# Power_Amp.net
KiCad netlist of a schematic drawn in Altium Designer
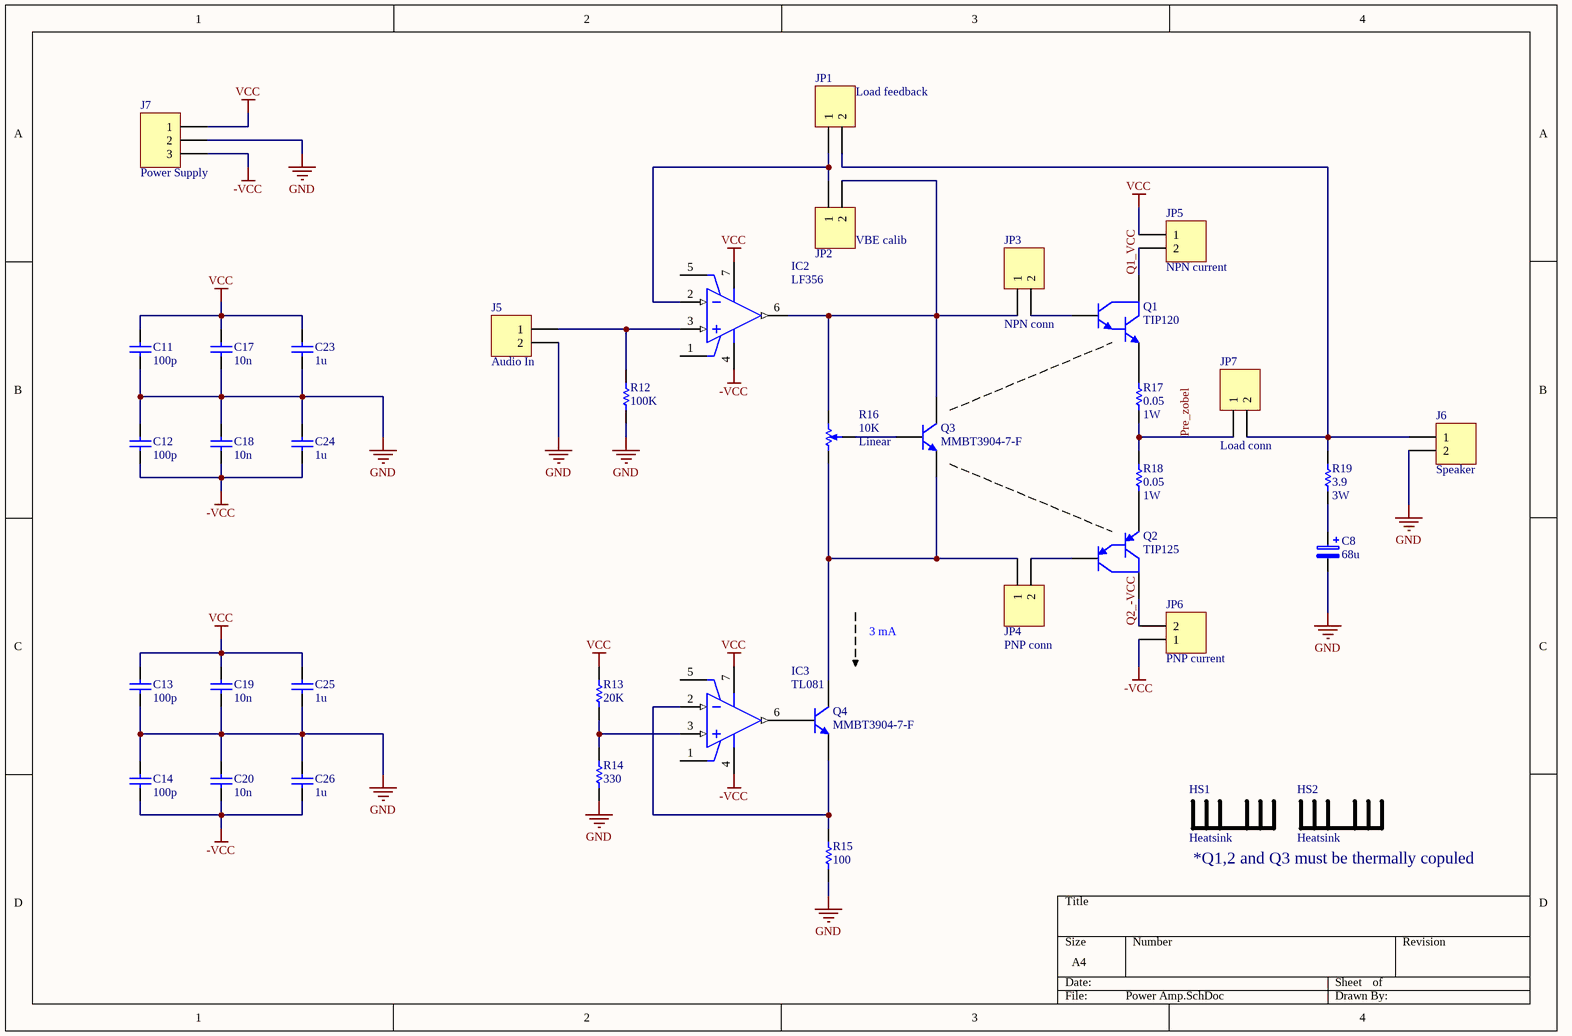
[diagram p0: Power Amp.SchDoc]

(export (version "E")
  (design (tool "Eeschema 10.0.6"))
  (components
    (comp (ref "C8")
      (value "68u")
      (footprint "CRADIAL-2.5mm")
      (description "Polarized Capacitor")
      (libsource (lib "nucleoduro_lib_audio") (part "Pol Capacitor"))
    )
    (comp (ref "C11")
      (value "100p")
      (footprint "C0805")
      (description "Capacitor")
      (libsource (lib "nucleoduro_lib_audio") (part "Capacitor"))
    )
    (comp (ref "C12")
      (value "100p")
      (footprint "C0805")
      (description "Capacitor")
      (libsource (lib "nucleoduro_lib_audio") (part "Capacitor"))
    )
    (comp (ref "C13")
      (value "100p")
      (footprint "C0805")
      (description "Capacitor")
      (libsource (lib "nucleoduro_lib_audio") (part "Capacitor"))
    )
    (comp (ref "C14")
      (value "100p")
      (footprint "C0805")
      (description "Capacitor")
      (libsource (lib "nucleoduro_lib_audio") (part "Capacitor"))
    )
    (comp (ref "C17")
      (value "10n")
      (footprint "C0805")
      (description "Capacitor")
      (libsource (lib "nucleoduro_lib_audio") (part "Capacitor"))
    )
    (comp (ref "C18")
      (value "10n")
      (footprint "C0805")
      (description "Capacitor")
      (libsource (lib "nucleoduro_lib_audio") (part "Capacitor"))
    )
    (comp (ref "C19")
      (value "10n")
      (footprint "C0805")
      (description "Capacitor")
      (libsource (lib "nucleoduro_lib_audio") (part "Capacitor"))
    )
    (comp (ref "C20")
      (value "10n")
      (footprint "C0805")
      (description "Capacitor")
      (libsource (lib "nucleoduro_lib_audio") (part "Capacitor"))
    )
    (comp (ref "C23")
      (value "1u")
      (footprint "C0805")
      (description "Capacitor")
      (libsource (lib "nucleoduro_lib_audio") (part "Capacitor"))
    )
    (comp (ref "C24")
      (value "1u")
      (footprint "C0805")
      (description "Capacitor")
      (libsource (lib "nucleoduro_lib_audio") (part "Capacitor"))
    )
    (comp (ref "C25")
      (value "1u")
      (footprint "C0805")
      (description "Capacitor")
      (libsource (lib "nucleoduro_lib_audio") (part "Capacitor"))
    )
    (comp (ref "C26")
      (value "1u")
      (footprint "C0805")
      (description "Capacitor")
      (libsource (lib "nucleoduro_lib_audio") (part "Capacitor"))
    )
    (comp (ref "HS1")
      (value "Heatsink")
      (footprint "MC33289")
      (description "Q1 Heatsink")
      (libsource (lib "nucleoduro_lib_audio") (part "Heatsink (MC33289)"))
    )
    (comp (ref "HS2")
      (value "Heatsink")
      (footprint "MC33289")
      (description "Q2 Heatsink")
      (libsource (lib "nucleoduro_lib_audio") (part "Heatsink (MC33289)"))
    )
    (comp (ref "IC2")
      (value "LF356")
      (footprint "SOIC127P600X175-8N")
      (libsource (lib "nucleoduro_lib_audio") (part "LF356"))
    )
    (comp (ref "IC3")
      (value "TL081")
      (footprint "SOIC127P600X175-8N")
      (libsource (lib "nucleoduro_lib_audio") (part "TL081"))
    )
    (comp (ref "J5")
      (value "Audio In")
      (footprint "2 Pin 5mm Terminal Block")
      (description "Terminal Block, 2 Pin")
      (libsource (lib "nucleoduro_lib_audio") (part "Terminal Block 2 Pin"))
    )
    (comp (ref "J6")
      (value "Speaker")
      (footprint "2 Pin 5mm Terminal Block")
      (description "Terminal Block, 2 Pin")
      (libsource (lib "") (part "Terminal Block 2 Pin_1"))
    )
    (comp (ref "J7")
      (value "Power Supply")
      (footprint "3 Pin 5mm Terminal Block")
      (description "Terminal Block, 3 Pin")
      (libsource (lib "nucleoduro_lib_audio") (part "Terminal Block 3 Pin"))
    )
    (comp (ref "JP1")
      (value "Load feedback")
      (footprint "HDR1X2")
      (description "Header, 2-Pin")
      (libsource (lib "nucleoduro_lib_audio") (part "Header 2"))
    )
    (comp (ref "JP2")
      (value "VBE calib")
      (footprint "HDR1X2")
      (description "Header, 2-Pin")
      (libsource (lib "") (part "Header 2_1"))
    )
    (comp (ref "JP3")
      (value "NPN conn")
      (footprint "HDR1X2")
      (description "Header, 2-Pin")
      (libsource (lib "nucleoduro_lib_audio") (part "Header 2"))
    )
    (comp (ref "JP4")
      (value "PNP conn")
      (footprint "HDR1X2")
      (description "Header, 2-Pin")
      (libsource (lib "") (part "Header 2_1"))
    )
    (comp (ref "JP5")
      (value "NPN current")
      (footprint "HDR1X2")
      (description "Header, 2-Pin")
      (libsource (lib "") (part "Header 2_2"))
    )
    (comp (ref "JP6")
      (value "PNP current")
      (footprint "HDR1X2")
      (description "Header, 2-Pin")
      (libsource (lib "nucleoduro_lib_audio") (part "Header 2"))
    )
    (comp (ref "JP7")
      (value "Load conn")
      (footprint "HDR1X2")
      (description "Header, 2-Pin")
      (libsource (lib "nucleoduro_lib_audio") (part "Header 2"))
    )
    (comp (ref "Q1")
      (value "TIP120")
      (footprint "TO-220")
      (description "NPN Darlington Bipolar Transistor")
      (libsource (lib "nucleoduro_lib_audio") (part "TIP120/121/122"))
    )
    (comp (ref "Q2")
      (value "TIP125")
      (footprint "TO-220")
      (description "PNP Darlington Bipolar Transistor")
      (libsource (lib "nucleoduro_lib_audio") (part "TIP125/126/127"))
    )
    (comp (ref "Q3")
      (value "MMBT3904-7-F")
      (footprint "SOT95P240X110-3N")
      (description "NPN General Purpose Amplifier SMD")
      (libsource (lib "nucleoduro_lib_audio") (part "MMBT3904-7-F"))
    )
    (comp (ref "Q4")
      (value "MMBT3904-7-F")
      (footprint "SOT95P240X110-3N")
      (description "NPN General Purpose Amplifier SMD")
      (libsource (lib "nucleoduro_lib_audio") (part "MMBT3904-7-F"))
    )
    (comp (ref "R12")
      (value "100K")
      (footprint "R0805")
      (description "Resistor")
      (libsource (lib "nucleoduro_lib_audio") (part "Resistor"))
    )
    (comp (ref "R13")
      (value "20K")
      (footprint "R0805")
      (description "Resistor")
      (libsource (lib "nucleoduro_lib_audio") (part "Resistor"))
    )
    (comp (ref "R14")
      (value "330")
      (footprint "R0805")
      (description "Resistor")
      (libsource (lib "nucleoduro_lib_audio") (part "Resistor"))
    )
    (comp (ref "R15")
      (value "100")
      (footprint "R0805")
      (description "Resistor")
      (libsource (lib "nucleoduro_lib_audio") (part "Resistor"))
    )
    (comp (ref "R16")
      (value "10K")
      (footprint "Res Pot Square Trimm")
      (description "Square Trimming Potentiometer")
      (fields (field (name "TYPE") "Linear"))
      (libsource (lib "nucleoduro_lib_audio") (part "Res Pot"))
    )
    (comp (ref "R17")
      (value "0.05")
      (footprint "R2512")
      (description "Resistor")
      (fields (field (name "POWER") "1W"))
      (libsource (lib "nucleoduro_lib_audio") (part "Resistor"))
    )
    (comp (ref "R18")
      (value "0.05")
      (footprint "R2512")
      (description "Resistor")
      (fields (field (name "POWER") "1W"))
      (libsource (lib "nucleoduro_lib_audio") (part "Resistor"))
    )
    (comp (ref "R19")
      (value "3.9")
      (footprint "RAXIAL-5mm-1mm")
      (description "Resistor")
      (fields (field (name "POWER") "3W"))
      (libsource (lib "nucleoduro_lib_audio") (part "Resistor"))
    )
  )
  (nets
    (net (code "1") (name "-VCC") (class "Default")
      (node (ref "C12") (pin "1") (pinfunction "1_1") (pintype "passive"))
      (node (ref "C14") (pin "1") (pinfunction "1_1") (pintype "passive"))
      (node (ref "C18") (pin "1") (pinfunction "1_1") (pintype "passive"))
      (node (ref "C20") (pin "1") (pinfunction "1_1") (pintype "passive"))
      (node (ref "C24") (pin "1") (pinfunction "1_1") (pintype "passive"))
      (node (ref "C26") (pin "1") (pinfunction "1_1") (pintype "passive"))
      (node (ref "IC2") (pin "4") (pinfunction "V-_4") (pintype "power_in"))
      (node (ref "IC3") (pin "4") (pinfunction "V-_4") (pintype "power_in"))
      (node (ref "J7") (pin "3") (pinfunction "3_3") (pintype "passive"))
      (node (ref "JP6") (pin "1") (pinfunction "1_1") (pintype "passive"))
    )
    (net (code "2") (name "/Pre_zobel") (class "Default")
      (node (ref "JP7") (pin "1") (pinfunction "1_1") (pintype "passive"))
      (node (ref "R17") (pin "1") (pinfunction "1_1") (pintype "passive"))
      (node (ref "R18") (pin "2") (pinfunction "2_2") (pintype "passive"))
    )
    (net (code "3") (name "/Q1_VCC") (class "Default")
      (node (ref "JP5") (pin "2") (pinfunction "2_2") (pintype "passive"))
      (node (ref "Q1") (pin "2") (pinfunction "C_2") (pintype "passive"))
    )
    (net (code "4") (name "/Q2_-VCC") (class "Default")
      (node (ref "JP6") (pin "2") (pinfunction "2_2") (pintype "passive"))
      (node (ref "Q2") (pin "2") (pinfunction "C_2") (pintype "passive"))
    )
    (net (code "5") (name "GND") (class "Default")
      (node (ref "C11") (pin "1") (pinfunction "1_1") (pintype "passive"))
      (node (ref "C12") (pin "2") (pinfunction "2_2") (pintype "passive"))
      (node (ref "C13") (pin "1") (pinfunction "1_1") (pintype "passive"))
      (node (ref "C14") (pin "2") (pinfunction "2_2") (pintype "passive"))
      (node (ref "C17") (pin "1") (pinfunction "1_1") (pintype "passive"))
      (node (ref "C18") (pin "2") (pinfunction "2_2") (pintype "passive"))
      (node (ref "C19") (pin "1") (pinfunction "1_1") (pintype "passive"))
      (node (ref "C20") (pin "2") (pinfunction "2_2") (pintype "passive"))
      (node (ref "C23") (pin "1") (pinfunction "1_1") (pintype "passive"))
      (node (ref "C24") (pin "2") (pinfunction "2_2") (pintype "passive"))
      (node (ref "C25") (pin "1") (pinfunction "1_1") (pintype "passive"))
      (node (ref "C26") (pin "2") (pinfunction "2_2") (pintype "passive"))
      (node (ref "C8") (pin "2") (pinfunction "2_2") (pintype "passive"))
      (node (ref "J5") (pin "2") (pinfunction "2_2") (pintype "passive"))
      (node (ref "J6") (pin "2") (pinfunction "2_2") (pintype "passive"))
      (node (ref "J7") (pin "2") (pinfunction "2_2") (pintype "passive"))
      (node (ref "R12") (pin "2") (pinfunction "2_2") (pintype "passive"))
      (node (ref "R14") (pin "1") (pinfunction "1_1") (pintype "passive"))
      (node (ref "R15") (pin "1") (pinfunction "1_1") (pintype "passive"))
    )
    (net (code "6") (name "Net-(C8-Pad1)") (class "Default")
      (node (ref "C8") (pin "1") (pinfunction "1_1") (pintype "passive"))
      (node (ref "R19") (pin "1") (pinfunction "1_1") (pintype "passive"))
    )
    (net (code "7") (name "Net-(IC2-IN+)") (class "Default")
      (node (ref "IC2") (pin "3") (pinfunction "IN+_3") (pintype "input"))
      (node (ref "J5") (pin "1") (pinfunction "1_1") (pintype "passive"))
      (node (ref "R12") (pin "1") (pinfunction "1_1") (pintype "passive"))
    )
    (net (code "8") (name "Net-(IC2-IN-)") (class "Default")
      (node (ref "IC2") (pin "2") (pinfunction "IN-_2") (pintype "input"))
      (node (ref "JP1") (pin "1") (pinfunction "1_1") (pintype "passive"))
      (node (ref "JP2") (pin "1") (pinfunction "1_1") (pintype "passive"))
    )
    (net (code "9") (name "Net-(IC2-OUT)") (class "Default")
      (node (ref "IC2") (pin "6") (pinfunction "OUT_6") (pintype "output"))
      (node (ref "JP2") (pin "2") (pinfunction "2_2") (pintype "passive"))
      (node (ref "JP3") (pin "1") (pinfunction "1_1") (pintype "passive"))
      (node (ref "Q3") (pin "3") (pinfunction "C_3") (pintype "passive"))
      (node (ref "R16") (pin "1") (pinfunction "1_1") (pintype "passive"))
    )
    (net (code "10") (name "Net-(IC3-IN+)") (class "Default")
      (node (ref "IC3") (pin "3") (pinfunction "IN+_3") (pintype "input"))
      (node (ref "R13") (pin "1") (pinfunction "1_1") (pintype "passive"))
      (node (ref "R14") (pin "2") (pinfunction "2_2") (pintype "passive"))
    )
    (net (code "11") (name "Net-(IC3-IN-)") (class "Default")
      (node (ref "IC3") (pin "2") (pinfunction "IN-_2") (pintype "input"))
      (node (ref "Q4") (pin "2") (pinfunction "E_2") (pintype "passive"))
      (node (ref "R15") (pin "2") (pinfunction "2_2") (pintype "passive"))
    )
    (net (code "12") (name "Net-(IC3-OUT)") (class "Default")
      (node (ref "IC3") (pin "6") (pinfunction "OUT_6") (pintype "output"))
      (node (ref "Q4") (pin "1") (pinfunction "B_1") (pintype "passive"))
    )
    (net (code "13") (name "Net-(J6-Pad1)") (class "Default")
      (node (ref "J6") (pin "1") (pinfunction "1_1") (pintype "passive"))
      (node (ref "JP1") (pin "2") (pinfunction "2_2") (pintype "passive"))
      (node (ref "JP7") (pin "2") (pinfunction "2_2") (pintype "passive"))
      (node (ref "R19") (pin "2") (pinfunction "2_2") (pintype "passive"))
    )
    (net (code "14") (name "Net-(Q1-B)") (class "Default")
      (node (ref "JP3") (pin "2") (pinfunction "2_2") (pintype "passive"))
      (node (ref "Q1") (pin "1") (pinfunction "B_1") (pintype "passive"))
    )
    (net (code "15") (name "Net-(Q1-E)") (class "Default")
      (node (ref "Q1") (pin "3") (pinfunction "E_3") (pintype "passive"))
      (node (ref "R17") (pin "2") (pinfunction "2_2") (pintype "passive"))
    )
    (net (code "16") (name "Net-(Q2-B)") (class "Default")
      (node (ref "JP4") (pin "2") (pinfunction "2_2") (pintype "passive"))
      (node (ref "Q2") (pin "1") (pinfunction "B_1") (pintype "passive"))
    )
    (net (code "17") (name "Net-(Q2-E)") (class "Default")
      (node (ref "Q2") (pin "3") (pinfunction "E_3") (pintype "passive"))
      (node (ref "R18") (pin "1") (pinfunction "1_1") (pintype "passive"))
    )
    (net (code "18") (name "Net-(Q3-B)") (class "Default")
      (node (ref "Q3") (pin "1") (pinfunction "B_1") (pintype "passive"))
      (node (ref "R16") (pin "2") (pinfunction "2_2") (pintype "passive"))
    )
    (net (code "19") (name "Net-(Q3-E)") (class "Default")
      (node (ref "JP4") (pin "1") (pinfunction "1_1") (pintype "passive"))
      (node (ref "Q3") (pin "2") (pinfunction "E_2") (pintype "passive"))
      (node (ref "Q4") (pin "3") (pinfunction "C_3") (pintype "passive"))
      (node (ref "R16") (pin "3") (pinfunction "3_3") (pintype "passive"))
    )
    (net (code "20") (name "VCC") (class "Default")
      (node (ref "C11") (pin "2") (pinfunction "2_2") (pintype "passive"))
      (node (ref "C13") (pin "2") (pinfunction "2_2") (pintype "passive"))
      (node (ref "C17") (pin "2") (pinfunction "2_2") (pintype "passive"))
      (node (ref "C19") (pin "2") (pinfunction "2_2") (pintype "passive"))
      (node (ref "C23") (pin "2") (pinfunction "2_2") (pintype "passive"))
      (node (ref "C25") (pin "2") (pinfunction "2_2") (pintype "passive"))
      (node (ref "IC2") (pin "7") (pinfunction "V+_7") (pintype "power_in"))
      (node (ref "IC3") (pin "7") (pinfunction "V+_7") (pintype "power_in"))
      (node (ref "J7") (pin "1") (pinfunction "1_1") (pintype "passive"))
      (node (ref "JP5") (pin "1") (pinfunction "1_1") (pintype "passive"))
      (node (ref "R13") (pin "2") (pinfunction "2_2") (pintype "passive"))
    )
    (net (code "21") (name "unconnected-(IC2-BALANCE1-Pad1)") (class "Default")
      (node (ref "IC2") (pin "1") (pinfunction "BALANCE1_1") (pintype "passive"))
    )
    (net (code "22") (name "unconnected-(IC2-BALANCE2-Pad5)") (class "Default")
      (node (ref "IC2") (pin "5") (pinfunction "BALANCE2_5") (pintype "passive"))
    )
    (net (code "23") (name "unconnected-(IC3-OFFSET_N1-Pad1)") (class "Default")
      (node (ref "IC3") (pin "1") (pinfunction "OFFSET_N1_1") (pintype "passive"))
    )
    (net (code "24") (name "unconnected-(IC3-OFFSET_N2-Pad5)") (class "Default")
      (node (ref "IC3") (pin "5") (pinfunction "OFFSET_N2_5") (pintype "passive"))
    )
  )
)
